# uv-meter.net
KiCad netlist of a schematic drawn in EAGLE
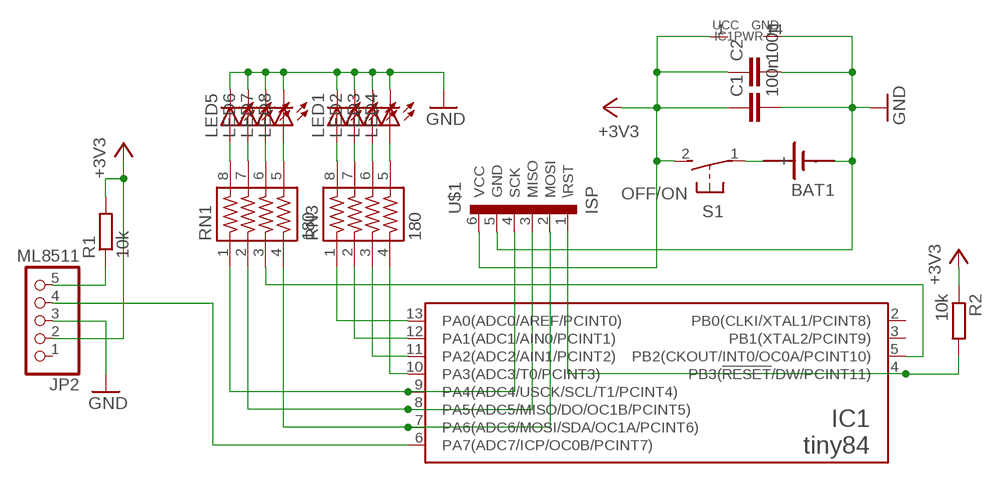
[diagram p0: schematic, sheet 1]

(export (version "E")
  (design (tool "Eeschema 10.0.6"))
  (components
    (comp (ref "BAT1")
      (value "SN2032")
      (footprint "eagle-import:SN2032")
      (libsource (lib "eagle-import") (part "SN2032"))
    )
    (comp (ref "C1")
      (value "100n")
      (footprint "eagle-import:C0805K")
      (libsource (lib "eagle-import") (part "C-EUC0805K"))
    )
    (comp (ref "C2")
      (value "100n")
      (footprint "eagle-import:C0805K")
      (libsource (lib "eagle-import") (part "C-EUC0805K"))
    )
    (comp (ref "IC1")
      (value "tiny84")
      (footprint "eagle-import:SOIC14")
      (libsource (lib "eagle-import") (part "ATTINY24/44/84-SSU"))
    )
    (comp (ref "JP2")
      (value "ML8511")
      (footprint "eagle-import:1X05")
      (libsource (lib "eagle-import") (part "PINHD-1X5"))
    )
    (comp (ref "LED1")
      (value "LEDSML0805")
      (footprint "eagle-import:SML0805")
      (libsource (lib "eagle-import") (part "LEDSML0805"))
    )
    (comp (ref "LED2")
      (value "LEDSML0805")
      (footprint "eagle-import:SML0805")
      (libsource (lib "eagle-import") (part "LEDSML0805"))
    )
    (comp (ref "LED3")
      (value "LEDSML0805")
      (footprint "eagle-import:SML0805")
      (libsource (lib "eagle-import") (part "LEDSML0805"))
    )
    (comp (ref "LED4")
      (value "LEDSML0805")
      (footprint "eagle-import:SML0805")
      (libsource (lib "eagle-import") (part "LEDSML0805"))
    )
    (comp (ref "LED5")
      (value "LEDSML0805")
      (footprint "eagle-import:SML0805")
      (libsource (lib "eagle-import") (part "LEDSML0805"))
    )
    (comp (ref "LED6")
      (value "LEDSML0805")
      (footprint "eagle-import:SML0805")
      (libsource (lib "eagle-import") (part "LEDSML0805"))
    )
    (comp (ref "LED7")
      (value "LEDSML0805")
      (footprint "eagle-import:SML0805")
      (libsource (lib "eagle-import") (part "LEDSML0805"))
    )
    (comp (ref "LED8")
      (value "LEDSML0805")
      (footprint "eagle-import:SML0805")
      (libsource (lib "eagle-import") (part "LEDSML0805"))
    )
    (comp (ref "R1")
      (value "10k")
      (footprint "eagle-import:M0805")
      (libsource (lib "eagle-import") (part "R-EU_M0805"))
    )
    (comp (ref "R2")
      (value "10k")
      (footprint "eagle-import:M0805")
      (libsource (lib "eagle-import") (part "R-EU_M0805"))
    )
    (comp (ref "RN1")
      (value "180")
      (footprint "eagle-import:744-8NS")
      (libsource (lib "eagle-import") (part "744-8NS"))
    )
    (comp (ref "RN3")
      (value "180")
      (footprint "eagle-import:744-8NS")
      (libsource (lib "eagle-import") (part "744-8NS"))
    )
    (comp (ref "S1")
      (value "OFF/ON")
      (footprint "eagle-import:DTS-3")
      (libsource (lib "eagle-import") (part "DTS-3"))
    )
    (comp (ref "U$1")
      (value "ISP")
      (footprint "eagle-import:POGOPROG-CONN")
      (libsource (lib "eagle-import") (part "POGOPIN-CONNSTANDARD"))
    )
  )
  (nets
    (net (code "1") (name "+3V3") (class "Default")
      (node (ref "C1") (pin "1") (pinfunction "1_1") (pintype "passive"))
      (node (ref "C2") (pin "1") (pinfunction "1_1") (pintype "passive"))
      (node (ref "IC1") (pin "1") (pinfunction "UCC_1") (pintype "power_in"))
      (node (ref "JP2") (pin "2") (pinfunction "2_2") (pintype "passive"))
      (node (ref "R1") (pin "2") (pinfunction "2_2") (pintype "passive"))
      (node (ref "R2") (pin "1") (pinfunction "1_1") (pintype "passive"))
      (node (ref "S1") (pin "2") (pinfunction "2_2") (pintype "passive"))
      (node (ref "U$1") (pin "6") (pinfunction "VCC_6") (pintype "bidirectional"))
    )
    (net (code "2") (name "GND") (class "Default")
      (node (ref "BAT1") (pin "-") (pinfunction "-_-") (pintype "passive"))
      (node (ref "C1") (pin "2") (pinfunction "2_2") (pintype "passive"))
      (node (ref "C2") (pin "2") (pinfunction "2_2") (pintype "passive"))
      (node (ref "IC1") (pin "14") (pinfunction "GND_14") (pintype "power_in"))
      (node (ref "JP2") (pin "3") (pinfunction "3_3") (pintype "passive"))
      (node (ref "LED1") (pin "C") (pinfunction "C_C") (pintype "passive"))
      (node (ref "LED2") (pin "C") (pinfunction "C_C") (pintype "passive"))
      (node (ref "LED3") (pin "C") (pinfunction "C_C") (pintype "passive"))
      (node (ref "LED4") (pin "C") (pinfunction "C_C") (pintype "passive"))
      (node (ref "LED5") (pin "C") (pinfunction "C_C") (pintype "passive"))
      (node (ref "LED6") (pin "C") (pinfunction "C_C") (pintype "passive"))
      (node (ref "LED7") (pin "C") (pinfunction "C_C") (pintype "passive"))
      (node (ref "LED8") (pin "C") (pinfunction "C_C") (pintype "passive"))
      (node (ref "U$1") (pin "5") (pinfunction "GND_5") (pintype "bidirectional"))
    )
    (net (code "3") (name "Net-(BAT1-Pad+)") (class "Default")
      (node (ref "BAT1") (pin "+") (pinfunction "+_+") (pintype "passive"))
      (node (ref "S1") (pin "1") (pinfunction "1_1") (pintype "passive"))
    )
    (net (code "4") (name "Net-(IC1A-PA0(ADC0{slash}AREF{slash}PCINT0))") (class "Default")
      (node (ref "IC1") (pin "13") (pinfunction "PA0(ADC0/AREF/PCINT0)_13") (pintype "bidirectional"))
      (node (ref "RN3") (pin "1") (pinfunction "1_1") (pintype "passive"))
    )
    (net (code "5") (name "Net-(IC1A-PA1(ADC1{slash}AIN0{slash}PCINT1))") (class "Default")
      (node (ref "IC1") (pin "12") (pinfunction "PA1(ADC1/AIN0/PCINT1)_12") (pintype "bidirectional"))
      (node (ref "RN3") (pin "2") (pinfunction "2_2") (pintype "passive"))
    )
    (net (code "6") (name "Net-(IC1A-PA2(ADC2{slash}AIN1{slash}PCINT2))") (class "Default")
      (node (ref "IC1") (pin "11") (pinfunction "PA2(ADC2/AIN1/PCINT2)_11") (pintype "bidirectional"))
      (node (ref "RN3") (pin "3") (pinfunction "3_3") (pintype "passive"))
    )
    (net (code "7") (name "Net-(IC1A-PA3(ADC3{slash}T0{slash}PCINT3))") (class "Default")
      (node (ref "IC1") (pin "10") (pinfunction "PA3(ADC3/T0/PCINT3)_10") (pintype "bidirectional"))
      (node (ref "RN3") (pin "4") (pinfunction "4_4") (pintype "passive"))
    )
    (net (code "8") (name "Net-(IC1A-PA4(ADC4{slash}USCK{slash}SCL{slash}T1{slash}PCINT4))") (class "Default")
      (node (ref "IC1") (pin "9") (pinfunction "PA4(ADC4/USCK/SCL/T1/PCINT4)_9") (pintype "bidirectional"))
      (node (ref "RN1") (pin "1") (pinfunction "1_1") (pintype "passive"))
      (node (ref "U$1") (pin "4") (pinfunction "SCK_4") (pintype "bidirectional"))
    )
    (net (code "9") (name "Net-(IC1A-PA5(ADC5{slash}MISO{slash}DO{slash}OC1B{slash}PCINT5))") (class "Default")
      (node (ref "IC1") (pin "8") (pinfunction "PA5(ADC5/MISO/DO/OC1B/PCINT5)_8") (pintype "bidirectional"))
      (node (ref "RN1") (pin "2") (pinfunction "2_2") (pintype "passive"))
      (node (ref "U$1") (pin "3") (pinfunction "MISO_3") (pintype "bidirectional"))
    )
    (net (code "10") (name "Net-(IC1A-PA6(ADC6{slash}MOSI{slash}SDA{slash}OC1A{slash}PCINT6))") (class "Default")
      (node (ref "IC1") (pin "7") (pinfunction "PA6(ADC6/MOSI/SDA/OC1A/PCINT6)_7") (pintype "bidirectional"))
      (node (ref "RN1") (pin "4") (pinfunction "4_4") (pintype "passive"))
      (node (ref "U$1") (pin "2") (pinfunction "MOSI_2") (pintype "bidirectional"))
    )
    (net (code "11") (name "Net-(IC1A-PA7(ADC7{slash}ICP{slash}OC0B{slash}PCINT7))") (class "Default")
      (node (ref "IC1") (pin "6") (pinfunction "PA7(ADC7/ICP/OC0B/PCINT7)_6") (pintype "bidirectional"))
      (node (ref "JP2") (pin "4") (pinfunction "4_4") (pintype "passive"))
    )
    (net (code "12") (name "Net-(IC1A-PB2(CKOUT{slash}INT0{slash}OC0A{slash}PCINT10))") (class "Default")
      (node (ref "IC1") (pin "5") (pinfunction "PB2(CKOUT/INT0/OC0A/PCINT10)_5") (pintype "bidirectional"))
      (node (ref "RN1") (pin "3") (pinfunction "3_3") (pintype "passive"))
    )
    (net (code "13") (name "Net-(IC1A-PB3(~{RESET}{slash}DW{slash}PCINT11))") (class "Default")
      (node (ref "IC1") (pin "4") (pinfunction "PB3(~{RESET}/DW/PCINT11)_4") (pintype "bidirectional"))
      (node (ref "R2") (pin "2") (pinfunction "2_2") (pintype "passive"))
      (node (ref "U$1") (pin "1") (pinfunction "\\RST_1") (pintype "bidirectional"))
    )
    (net (code "14") (name "Net-(JP2-Pad5)") (class "Default")
      (node (ref "JP2") (pin "5") (pinfunction "5_5") (pintype "passive"))
      (node (ref "R1") (pin "1") (pinfunction "1_1") (pintype "passive"))
    )
    (net (code "15") (name "Net-(LED1-PadA)") (class "Default")
      (node (ref "LED1") (pin "A") (pinfunction "A_A") (pintype "passive"))
      (node (ref "RN3") (pin "8") (pinfunction "8_8") (pintype "passive"))
    )
    (net (code "16") (name "Net-(LED2-PadA)") (class "Default")
      (node (ref "LED2") (pin "A") (pinfunction "A_A") (pintype "passive"))
      (node (ref "RN3") (pin "7") (pinfunction "7_7") (pintype "passive"))
    )
    (net (code "17") (name "Net-(LED3-PadA)") (class "Default")
      (node (ref "LED3") (pin "A") (pinfunction "A_A") (pintype "passive"))
      (node (ref "RN3") (pin "6") (pinfunction "6_6") (pintype "passive"))
    )
    (net (code "18") (name "Net-(LED4-PadA)") (class "Default")
      (node (ref "LED4") (pin "A") (pinfunction "A_A") (pintype "passive"))
      (node (ref "RN3") (pin "5") (pinfunction "5_5") (pintype "passive"))
    )
    (net (code "19") (name "Net-(LED5-PadA)") (class "Default")
      (node (ref "LED5") (pin "A") (pinfunction "A_A") (pintype "passive"))
      (node (ref "RN1") (pin "8") (pinfunction "8_8") (pintype "passive"))
    )
    (net (code "20") (name "Net-(LED6-PadA)") (class "Default")
      (node (ref "LED6") (pin "A") (pinfunction "A_A") (pintype "passive"))
      (node (ref "RN1") (pin "7") (pinfunction "7_7") (pintype "passive"))
    )
    (net (code "21") (name "Net-(LED7-PadA)") (class "Default")
      (node (ref "LED7") (pin "A") (pinfunction "A_A") (pintype "passive"))
      (node (ref "RN1") (pin "6") (pinfunction "6_6") (pintype "passive"))
    )
    (net (code "22") (name "Net-(LED8-PadA)") (class "Default")
      (node (ref "LED8") (pin "A") (pinfunction "A_A") (pintype "passive"))
      (node (ref "RN1") (pin "5") (pinfunction "5_5") (pintype "passive"))
    )
    (net (code "23") (name "unconnected-(IC1A-PB0(CLKI{slash}XTAL1{slash}PCINT8)-Pad2)") (class "Default")
      (node (ref "IC1") (pin "2") (pinfunction "PB0(CLKI/XTAL1/PCINT8)_2") (pintype "bidirectional"))
    )
    (net (code "24") (name "unconnected-(IC1A-PB1(XTAL2{slash}PCINT9)-Pad3)") (class "Default")
      (node (ref "IC1") (pin "3") (pinfunction "PB1(XTAL2/PCINT9)_3") (pintype "bidirectional"))
    )
    (net (code "25") (name "unconnected-(JP2-Pad1)") (class "Default")
      (node (ref "JP2") (pin "1") (pinfunction "1_1") (pintype "passive"))
    )
  )
)
